# mk2_5.net
KiCad netlist of a schematic drawn in EAGLE
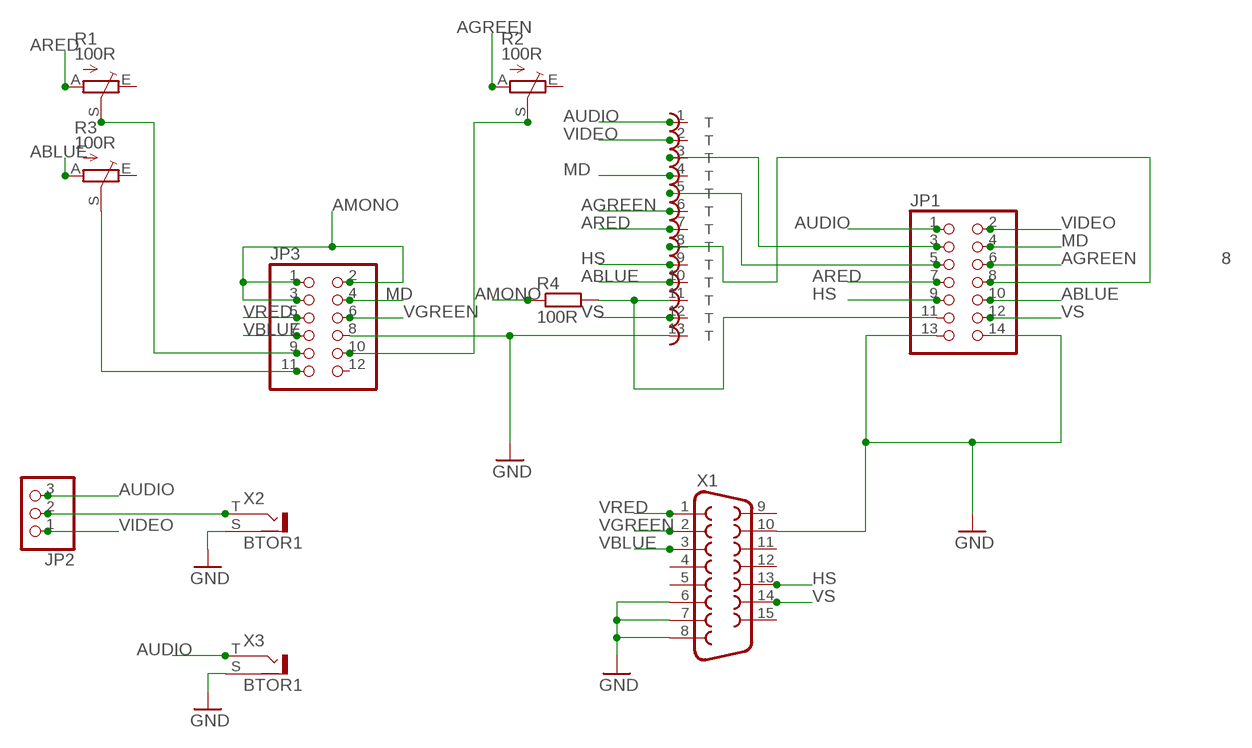
[diagram p0: schematic, sheet 1]

(export (version "E")
  (design (tool "Eeschema 10.0.6"))
  (components
    (comp (ref "J1")
      (value "DIN13T")
      (footprint "eagle-import:ADADS")
      (libsource (lib "eagle-import") (part "DIN13T"))
    )
    (comp (ref "JP1")
      (value "PINHD-2X7")
      (footprint "eagle-import:2X07")
      (libsource (lib "eagle-import") (part "PINHD-2X7"))
    )
    (comp (ref "JP2")
      (value "PINHD-1X3")
      (footprint "eagle-import:1X03")
      (libsource (lib "eagle-import") (part "PINHD-1X3"))
    )
    (comp (ref "JP3")
      (value "PINHD-2X6")
      (footprint "eagle-import:2X06")
      (libsource (lib "eagle-import") (part "PINHD-2X6"))
    )
    (comp (ref "R1")
      (value "100R")
      (footprint "eagle-import:CA6H")
      (libsource (lib "eagle-import") (part "TRIM_EU-CA6H"))
    )
    (comp (ref "R2")
      (value "100R")
      (footprint "eagle-import:CA6H")
      (libsource (lib "eagle-import") (part "TRIM_EU-CA6H"))
    )
    (comp (ref "R3")
      (value "100R")
      (footprint "eagle-import:CA6H")
      (libsource (lib "eagle-import") (part "TRIM_EU-CA6H"))
    )
    (comp (ref "R4")
      (value "100R")
      (footprint "eagle-import:0204_5")
      (libsource (lib "eagle-import") (part "R-EU_0204/5"))
    )
    (comp (ref "X1")
      (value "F15HDV")
      (footprint "eagle-import:HDF15V")
      (libsource (lib "eagle-import") (part "F15HDV"))
    )
    (comp (ref "X2")
      (value "BTOR1")
      (footprint "eagle-import:BTOR1")
      (libsource (lib "eagle-import") (part "BTOR1"))
    )
    (comp (ref "X3")
      (value "BTOR1")
      (footprint "eagle-import:BTOR1")
      (libsource (lib "eagle-import") (part "BTOR1"))
    )
  )
  (nets
    (net (code "1") (name "/8") (class "Default")
      (node (ref "J1") (pin "8") (pinfunction "T_8") (pintype "passive"))
      (node (ref "JP1") (pin "8") (pinfunction "8_8") (pintype "passive"))
    )
    (net (code "2") (name "/ABLUE") (class "Default")
      (node (ref "J1") (pin "10") (pinfunction "T_10") (pintype "passive"))
      (node (ref "JP1") (pin "10") (pinfunction "10_10") (pintype "passive"))
      (node (ref "R3") (pin "A") (pinfunction "A_A") (pintype "passive"))
    )
    (net (code "3") (name "/AGREEN") (class "Default")
      (node (ref "J1") (pin "6") (pinfunction "T_6") (pintype "passive"))
      (node (ref "JP1") (pin "6") (pinfunction "6_6") (pintype "passive"))
      (node (ref "R2") (pin "A") (pinfunction "A_A") (pintype "passive"))
    )
    (net (code "4") (name "/AMONO") (class "Default")
      (node (ref "JP3") (pin "1") (pinfunction "1_1") (pintype "passive"))
      (node (ref "JP3") (pin "2") (pinfunction "2_2") (pintype "passive"))
      (node (ref "JP3") (pin "3") (pinfunction "3_3") (pintype "passive"))
      (node (ref "R4") (pin "1") (pinfunction "1_1") (pintype "passive"))
    )
    (net (code "5") (name "/ARED") (class "Default")
      (node (ref "J1") (pin "7") (pinfunction "T_7") (pintype "passive"))
      (node (ref "JP1") (pin "7") (pinfunction "7_7") (pintype "passive"))
      (node (ref "R1") (pin "A") (pinfunction "A_A") (pintype "passive"))
    )
    (net (code "6") (name "/AUDIO") (class "Default")
      (node (ref "J1") (pin "1") (pinfunction "T_1") (pintype "passive"))
      (node (ref "JP1") (pin "1") (pinfunction "1_1") (pintype "passive"))
      (node (ref "JP2") (pin "3") (pinfunction "3_3") (pintype "passive"))
      (node (ref "X3") (pin "T") (pinfunction "1_T") (pintype "passive"))
    )
    (net (code "7") (name "/HS") (class "Default")
      (node (ref "J1") (pin "9") (pinfunction "T_9") (pintype "passive"))
      (node (ref "JP1") (pin "9") (pinfunction "9_9") (pintype "passive"))
      (node (ref "X1") (pin "13") (pinfunction "13_13") (pintype "passive"))
    )
    (net (code "8") (name "/MD") (class "Default")
      (node (ref "J1") (pin "4") (pinfunction "T_4") (pintype "passive"))
      (node (ref "JP1") (pin "4") (pinfunction "4_4") (pintype "passive"))
      (node (ref "JP3") (pin "4") (pinfunction "4_4") (pintype "passive"))
    )
    (net (code "9") (name "/VBLUE") (class "Default")
      (node (ref "JP3") (pin "7") (pinfunction "7_7") (pintype "passive"))
      (node (ref "X1") (pin "3") (pinfunction "3_3") (pintype "passive"))
    )
    (net (code "10") (name "/VGREEN") (class "Default")
      (node (ref "JP3") (pin "6") (pinfunction "6_6") (pintype "passive"))
      (node (ref "X1") (pin "2") (pinfunction "2_2") (pintype "passive"))
    )
    (net (code "11") (name "/VIDEO") (class "Default")
      (node (ref "J1") (pin "2") (pinfunction "T_2") (pintype "passive"))
      (node (ref "JP1") (pin "2") (pinfunction "2_2") (pintype "passive"))
      (node (ref "JP2") (pin "1") (pinfunction "1_1") (pintype "passive"))
    )
    (net (code "12") (name "/VRED") (class "Default")
      (node (ref "JP3") (pin "5") (pinfunction "5_5") (pintype "passive"))
      (node (ref "X1") (pin "1") (pinfunction "1_1") (pintype "passive"))
    )
    (net (code "13") (name "/VS") (class "Default")
      (node (ref "J1") (pin "12") (pinfunction "T_12") (pintype "passive"))
      (node (ref "JP1") (pin "12") (pinfunction "12_12") (pintype "passive"))
      (node (ref "X1") (pin "14") (pinfunction "14_14") (pintype "passive"))
    )
    (net (code "14") (name "GND") (class "Default")
      (node (ref "J1") (pin "13") (pinfunction "T_13") (pintype "passive"))
      (node (ref "JP1") (pin "13") (pinfunction "13_13") (pintype "passive"))
      (node (ref "JP1") (pin "14") (pinfunction "14_14") (pintype "passive"))
      (node (ref "JP3") (pin "8") (pinfunction "8_8") (pintype "passive"))
      (node (ref "X1") (pin "10") (pinfunction "10_10") (pintype "passive"))
      (node (ref "X1") (pin "6") (pinfunction "6_6") (pintype "passive"))
      (node (ref "X1") (pin "7") (pinfunction "7_7") (pintype "passive"))
      (node (ref "X1") (pin "8") (pinfunction "8_8") (pintype "passive"))
      (node (ref "X2") (pin "S") (pinfunction "2_S") (pintype "passive"))
      (node (ref "X3") (pin "S") (pinfunction "2_S") (pintype "passive"))
    )
    (net (code "15") (name "Net-(J1C-T)") (class "Default")
      (node (ref "J1") (pin "11") (pinfunction "T_11") (pintype "passive"))
      (node (ref "JP1") (pin "11") (pinfunction "11_11") (pintype "passive"))
      (node (ref "R4") (pin "2") (pinfunction "2_2") (pintype "passive"))
    )
    (net (code "16") (name "Net-(J1G-T)") (class "Default")
      (node (ref "J1") (pin "3") (pinfunction "T_3") (pintype "passive"))
      (node (ref "JP1") (pin "3") (pinfunction "3_3") (pintype "passive"))
    )
    (net (code "17") (name "Net-(J1I-T)") (class "Default")
      (node (ref "J1") (pin "5") (pinfunction "T_5") (pintype "passive"))
      (node (ref "JP1") (pin "5") (pinfunction "5_5") (pintype "passive"))
    )
    (net (code "18") (name "Net-(JP3-Pad9)") (class "Default")
      (node (ref "JP3") (pin "9") (pinfunction "9_9") (pintype "passive"))
      (node (ref "R1") (pin "S") (pinfunction "S_S") (pintype "passive"))
    )
    (net (code "19") (name "Net-(JP3-Pad10)") (class "Default")
      (node (ref "JP3") (pin "10") (pinfunction "10_10") (pintype "passive"))
      (node (ref "R2") (pin "S") (pinfunction "S_S") (pintype "passive"))
    )
    (net (code "20") (name "Net-(JP3-Pad11)") (class "Default")
      (node (ref "JP3") (pin "11") (pinfunction "11_11") (pintype "passive"))
      (node (ref "R3") (pin "S") (pinfunction "S_S") (pintype "passive"))
    )
    (net (code "21") (name "Net-(X2-1)") (class "Default")
      (node (ref "JP2") (pin "2") (pinfunction "2_2") (pintype "passive"))
      (node (ref "X2") (pin "T") (pinfunction "1_T") (pintype "passive"))
    )
    (net (code "22") (name "unconnected-(JP3-Pad12)") (class "Default")
      (node (ref "JP3") (pin "12") (pinfunction "12_12") (pintype "passive"))
    )
    (net (code "23") (name "unconnected-(R1-PadE)") (class "Default")
      (node (ref "R1") (pin "E") (pinfunction "E_E") (pintype "passive"))
    )
    (net (code "24") (name "unconnected-(R2-PadE)") (class "Default")
      (node (ref "R2") (pin "E") (pinfunction "E_E") (pintype "passive"))
    )
    (net (code "25") (name "unconnected-(R3-PadE)") (class "Default")
      (node (ref "R3") (pin "E") (pinfunction "E_E") (pintype "passive"))
    )
    (net (code "26") (name "unconnected-(X1-Pad4)") (class "Default")
      (node (ref "X1") (pin "4") (pinfunction "4_4") (pintype "passive"))
    )
    (net (code "27") (name "unconnected-(X1-Pad5)") (class "Default")
      (node (ref "X1") (pin "5") (pinfunction "5_5") (pintype "passive"))
    )
    (net (code "28") (name "unconnected-(X1-Pad9)") (class "Default")
      (node (ref "X1") (pin "9") (pinfunction "9_9") (pintype "passive"))
    )
    (net (code "29") (name "unconnected-(X1-Pad11)") (class "Default")
      (node (ref "X1") (pin "11") (pinfunction "11_11") (pintype "passive"))
    )
    (net (code "30") (name "unconnected-(X1-Pad12)") (class "Default")
      (node (ref "X1") (pin "12") (pinfunction "12_12") (pintype "passive"))
    )
    (net (code "31") (name "unconnected-(X1-Pad15)") (class "Default")
      (node (ref "X1") (pin "15") (pinfunction "15_15") (pintype "passive"))
    )
    (net (code "32") (name "unconnected-(X2-2-PadS@1)") (class "Default")
      (node (ref "X2") (pin "S@1") (pinfunction "2_S@1") (pintype "passive"))
    )
    (net (code "33") (name "unconnected-(X2-2-PadS@2)") (class "Default")
      (node (ref "X2") (pin "S@2") (pinfunction "2_S@2") (pintype "passive"))
    )
    (net (code "34") (name "unconnected-(X2-2-PadS@3)") (class "Default")
      (node (ref "X2") (pin "S@3") (pinfunction "2_S@3") (pintype "passive"))
    )
    (net (code "35") (name "unconnected-(X3-2-PadS@1)") (class "Default")
      (node (ref "X3") (pin "S@1") (pinfunction "2_S@1") (pintype "passive"))
    )
    (net (code "36") (name "unconnected-(X3-2-PadS@2)") (class "Default")
      (node (ref "X3") (pin "S@2") (pinfunction "2_S@2") (pintype "passive"))
    )
    (net (code "37") (name "unconnected-(X3-2-PadS@3)") (class "Default")
      (node (ref "X3") (pin "S@3") (pinfunction "2_S@3") (pintype "passive"))
    )
  )
)
